# electronic-connection.net
KiCad netlist of a schematic drawn in EAGLE
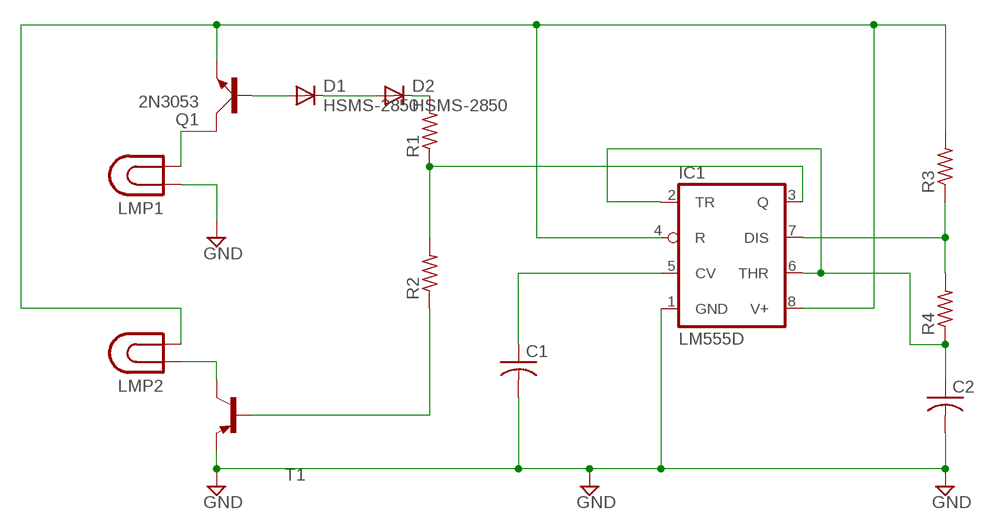
[diagram p0: schematic, sheet 1]

(export (version "E")
  (design (tool "Eeschema 10.0.6"))
  (components
    (comp (ref "C1")
      (value "C-US025-024X044")
      (footprint "eagle-import:C025-024X044")
      (libsource (lib "eagle-import") (part "C-US025-024X044"))
    )
    (comp (ref "C2")
      (value "C-US025-024X044")
      (footprint "eagle-import:C025-024X044")
      (libsource (lib "eagle-import") (part "C-US025-024X044"))
    )
    (comp (ref "D1")
      (value "HSMS-2850")
      (footprint "eagle-import:SOT23")
      (libsource (lib "eagle-import") (part "HSMS-2850"))
    )
    (comp (ref "D2")
      (value "HSMS-2850")
      (footprint "eagle-import:SOT23")
      (libsource (lib "eagle-import") (part "HSMS-2850"))
    )
    (comp (ref "IC1")
      (value "LM555D")
      (footprint "eagle-import:SO08")
      (libsource (lib "eagle-import") (part "555DLM"))
    )
    (comp (ref "LMP1")
      (value "LAMP")
      (footprint "eagle-import:LDH-5R")
      (libsource (lib "eagle-import") (part "LAMP"))
    )
    (comp (ref "LMP2")
      (value "LAMP")
      (footprint "eagle-import:LDH-5R")
      (libsource (lib "eagle-import") (part "LAMP"))
    )
    (comp (ref "Q1")
      (value "2N3053")
      (footprint "eagle-import:TO39")
      (libsource (lib "eagle-import") (part "2N3053"))
    )
    (comp (ref "R1")
      (value "R-US_0204/2V")
      (footprint "eagle-import:0204V")
      (libsource (lib "eagle-import") (part "R-US_0204/2V"))
    )
    (comp (ref "R2")
      (value "R-US_0204/2V")
      (footprint "eagle-import:0204V")
      (libsource (lib "eagle-import") (part "R-US_0204/2V"))
    )
    (comp (ref "R3")
      (value "R-US_0204/2V")
      (footprint "eagle-import:0204V")
      (libsource (lib "eagle-import") (part "R-US_0204/2V"))
    )
    (comp (ref "R4")
      (value "R-US_0204/2V")
      (footprint "eagle-import:0204V")
      (libsource (lib "eagle-import") (part "R-US_0204/2V"))
    )
    (comp (ref "T1")
      (value "2N2905-PNP-TO39-EBC")
      (footprint "eagle-import:TO39")
      (libsource (lib "eagle-import") (part "-PNP-TO39-EBC2N2905"))
    )
  )
  (nets
    (net (code "1") (name "GND") (class "Default")
      (node (ref "C1") (pin "2") (pinfunction "2_2") (pintype "passive"))
      (node (ref "C2") (pin "2") (pinfunction "2_2") (pintype "passive"))
      (node (ref "IC1") (pin "1") (pinfunction "GND_1") (pintype "power_in"))
      (node (ref "LMP1") (pin "1") (pinfunction "1_1") (pintype "passive"))
      (node (ref "T1") (pin "1") (pinfunction "E_1") (pintype "passive"))
    )
    (net (code "2") (name "Net-(D1-A)") (class "Default")
      (node (ref "D1") (pin "1") (pinfunction "A_1") (pintype "passive"))
      (node (ref "Q1") (pin "2") (pinfunction "B_2") (pintype "passive"))
    )
    (net (code "3") (name "Net-(D1-C)") (class "Default")
      (node (ref "D1") (pin "3") (pinfunction "C_3") (pintype "passive"))
      (node (ref "D2") (pin "1") (pinfunction "A_1") (pintype "passive"))
    )
    (net (code "4") (name "Net-(D2-C)") (class "Default")
      (node (ref "D2") (pin "3") (pinfunction "C_3") (pintype "passive"))
      (node (ref "R1") (pin "2") (pinfunction "2_2") (pintype "passive"))
    )
    (net (code "5") (name "Net-(IC1-CV)") (class "Default")
      (node (ref "C1") (pin "1") (pinfunction "1_1") (pintype "passive"))
      (node (ref "IC1") (pin "5") (pinfunction "CV_5") (pintype "input"))
    )
    (net (code "6") (name "Net-(IC1-DIS)") (class "Default")
      (node (ref "IC1") (pin "7") (pinfunction "DIS_7") (pintype "input"))
      (node (ref "R3") (pin "1") (pinfunction "1_1") (pintype "passive"))
      (node (ref "R4") (pin "2") (pinfunction "2_2") (pintype "passive"))
    )
    (net (code "7") (name "Net-(IC1-Q)") (class "Default")
      (node (ref "IC1") (pin "3") (pinfunction "Q_3") (pintype "output"))
      (node (ref "R1") (pin "1") (pinfunction "1_1") (pintype "passive"))
      (node (ref "R2") (pin "2") (pinfunction "2_2") (pintype "passive"))
    )
    (net (code "8") (name "Net-(IC1-R)") (class "Default")
      (node (ref "IC1") (pin "4") (pinfunction "R_4") (pintype "input"))
      (node (ref "IC1") (pin "8") (pinfunction "V+_8") (pintype "power_in"))
      (node (ref "LMP2") (pin "2") (pinfunction "2_2") (pintype "passive"))
      (node (ref "Q1") (pin "1") (pinfunction "E_1") (pintype "passive"))
      (node (ref "R3") (pin "2") (pinfunction "2_2") (pintype "passive"))
    )
    (net (code "9") (name "Net-(IC1-THR)") (class "Default")
      (node (ref "C2") (pin "1") (pinfunction "1_1") (pintype "passive"))
      (node (ref "IC1") (pin "2") (pinfunction "TR_2") (pintype "input"))
      (node (ref "IC1") (pin "6") (pinfunction "THR_6") (pintype "input"))
      (node (ref "R4") (pin "1") (pinfunction "1_1") (pintype "passive"))
    )
    (net (code "10") (name "Net-(Q1-C)") (class "Default")
      (node (ref "LMP1") (pin "2") (pinfunction "2_2") (pintype "passive"))
      (node (ref "Q1") (pin "3") (pinfunction "C_3") (pintype "passive"))
    )
    (net (code "11") (name "Net-(T1-B)") (class "Default")
      (node (ref "R2") (pin "1") (pinfunction "1_1") (pintype "passive"))
      (node (ref "T1") (pin "2") (pinfunction "B_2") (pintype "passive"))
    )
    (net (code "12") (name "Net-(T1-C)") (class "Default")
      (node (ref "LMP2") (pin "1") (pinfunction "1_1") (pintype "passive"))
      (node (ref "T1") (pin "3") (pinfunction "C_3") (pintype "passive"))
    )
  )
)
